# Sheet1_GMAX0505_MB.net
KiCad netlist of a schematic drawn in Altium Designer
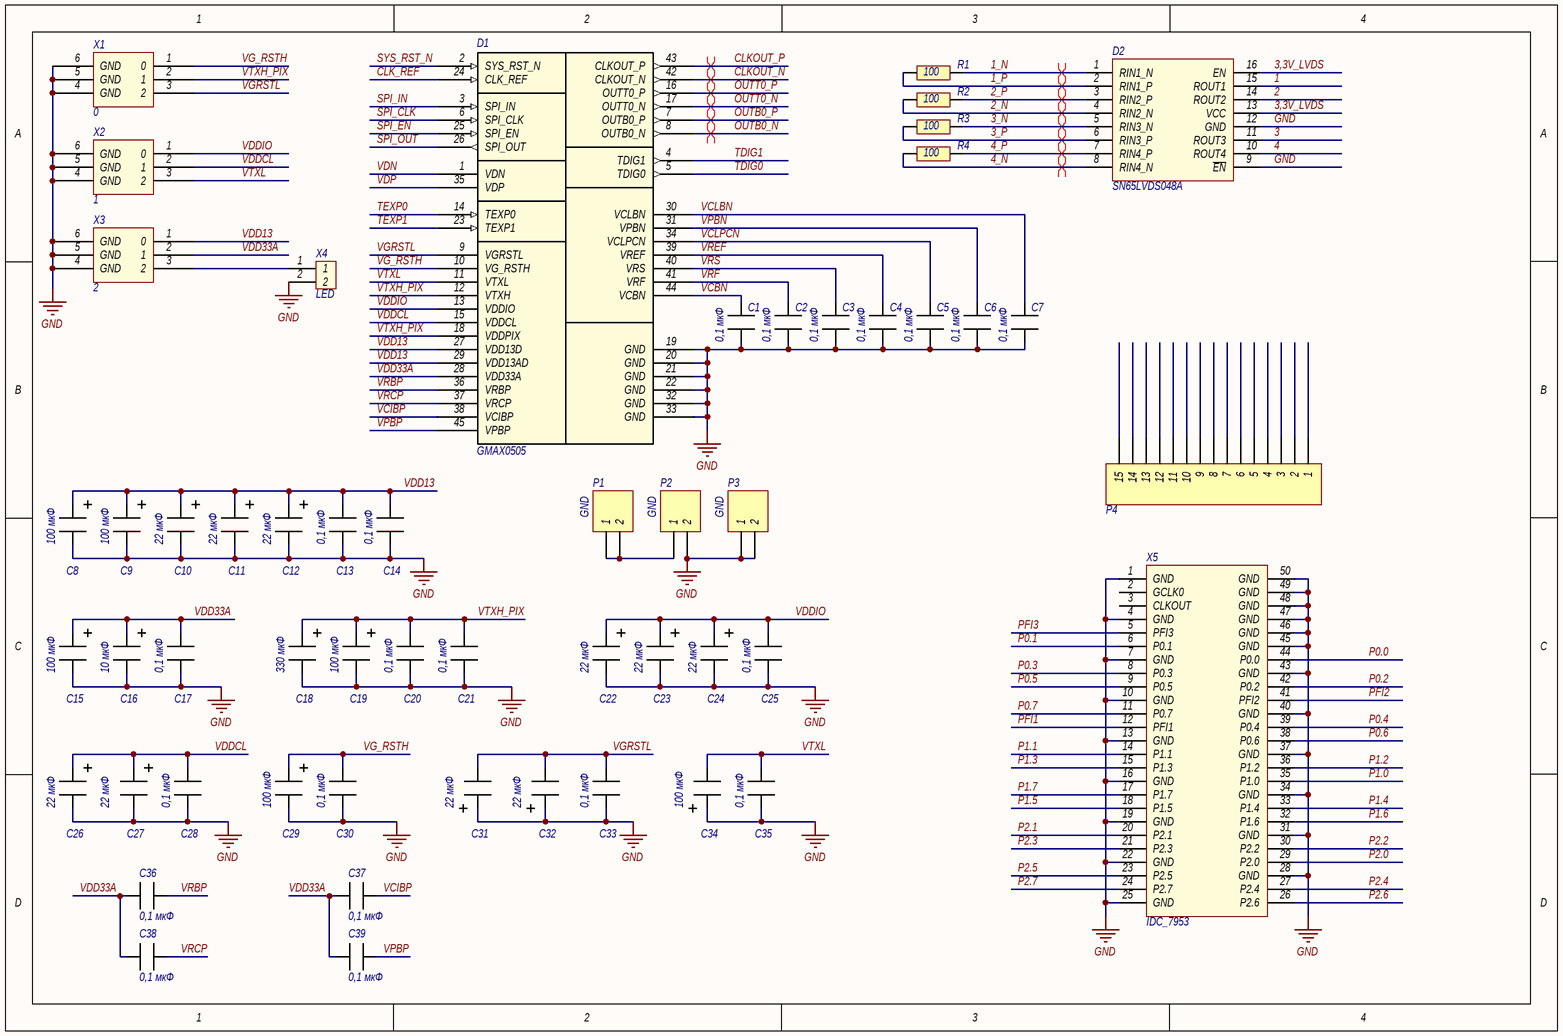
[diagram p0: Sheet1_GMAX0505_MB.SchDoc]

(export (version "E")
  (design (tool "Eeschema 10.0.6"))
  (components
    (comp (ref "C1") (value "0,1 мкФ") (footprint "CAP_SMALL") (libsource (lib "Schlib") (part "CAP_SMALL")))
    (comp (ref "C2") (value "0,1 мкФ") (footprint "CAP_SMALL") (libsource (lib "Schlib") (part "CAP_SMALL")))
    (comp (ref "C3") (value "0,1 мкФ") (footprint "CAP_SMALL") (libsource (lib "Schlib") (part "CAP_SMALL")))
    (comp (ref "C4") (value "0,1 мкФ") (footprint "CAP_SMALL") (libsource (lib "Schlib") (part "CAP_SMALL")))
    (comp (ref "C5") (value "0,1 мкФ") (footprint "CAP_SMALL") (libsource (lib "Schlib") (part "CAP_SMALL")))
    (comp (ref "C6") (value "0,1 мкФ") (footprint "CAP_SMALL") (libsource (lib "Schlib") (part "CAP_SMALL")))
    (comp (ref "C7") (value "0,1 мкФ") (footprint "CAP_SMALL") (libsource (lib "Schlib") (part "CAP_SMALL")))
    (comp (ref "C8")
      (value "100 мкФ")
      (footprint "Cap_0612_electrolitic")
      (libsource (lib "Schlib") (part "Cap_electrolotoc_0612"))
    )
    (comp (ref "C9")
      (value "100 мкФ")
      (footprint "Cap_0612_electrolitic")
      (libsource (lib "Schlib") (part "Cap_electrolotoc_0612"))
    )
    (comp (ref "C10")
      (value "22 мкФ")
      (footprint "Cap_0511_electrolitic")
      (libsource (lib "Schlib") (part "Cap_electrolotoc_0511"))
    )
    (comp (ref "C11")
      (value "22 мкФ")
      (footprint "Cap_0511_electrolitic")
      (libsource (lib "Schlib") (part "Cap_electrolotoc_0511"))
    )
    (comp (ref "C12")
      (value "22 мкФ")
      (footprint "Cap_0511_electrolitic")
      (libsource (lib "Schlib") (part "Cap_electrolotoc_0511"))
    )
    (comp (ref "C13") (value "0,1 мкФ") (footprint "CAP_SMALL") (libsource (lib "Schlib") (part "CAP_SMALL")))
    (comp (ref "C14") (value "0,1 мкФ") (footprint "CAP_SMALL") (libsource (lib "Schlib") (part "CAP_SMALL")))
    (comp (ref "C15")
      (value "100 мкФ")
      (footprint "Cap_0612_electrolitic")
      (libsource (lib "Schlib") (part "Cap_electrolotoc_0612"))
    )
    (comp (ref "C16")
      (value "10 мкФ")
      (footprint "Cap_0511_electrolitic")
      (libsource (lib "Schlib") (part "Cap_electrolotoc_0511"))
    )
    (comp (ref "C17") (value "0,1 мкФ") (footprint "CAP_SMALL") (libsource (lib "Schlib") (part "CAP_SMALL")))
    (comp (ref "C18")
      (value "330 мкФ")
      (footprint "Cap_1013_electrolitic")
      (libsource (lib "Schlib") (part "Cap_electrolotoc_1013"))
    )
    (comp (ref "C19")
      (value "100 мкФ")
      (footprint "Cap_0612_electrolitic")
      (libsource (lib "Schlib") (part "Cap_electrolotoc_0612"))
    )
    (comp (ref "C20") (value "0,1 мкФ") (footprint "CAP_SMALL") (libsource (lib "Schlib") (part "CAP_SMALL")))
    (comp (ref "C21") (value "0,1 мкФ") (footprint "CAP_SMALL") (libsource (lib "Schlib") (part "CAP_SMALL")))
    (comp (ref "C22")
      (value "22 мкФ")
      (footprint "Cap_0511_electrolitic")
      (libsource (lib "Schlib") (part "Cap_electrolotoc_0511"))
    )
    (comp (ref "C23")
      (value "22 мкФ")
      (footprint "Cap_0511_electrolitic")
      (libsource (lib "Schlib") (part "Cap_electrolotoc_0511"))
    )
    (comp (ref "C24")
      (value "22 мкФ")
      (footprint "Cap_0511_electrolitic")
      (libsource (lib "Schlib") (part "Cap_electrolotoc_0511"))
    )
    (comp (ref "C25") (value "0,1 мкФ") (footprint "CAP_SMALL") (libsource (lib "Schlib") (part "CAP_SMALL")))
    (comp (ref "C26")
      (value "22 мкФ")
      (footprint "Cap_0511_electrolitic")
      (libsource (lib "Schlib") (part "Cap_electrolotoc_0511"))
    )
    (comp (ref "C27")
      (value "22 мкФ")
      (footprint "Cap_0511_electrolitic")
      (libsource (lib "Schlib") (part "Cap_electrolotoc_0511"))
    )
    (comp (ref "C28") (value "0,1 мкФ") (footprint "CAP_SMALL") (libsource (lib "Schlib") (part "CAP_SMALL")))
    (comp (ref "C29")
      (value "100 мкФ")
      (footprint "Cap_0612_electrolitic")
      (libsource (lib "Schlib") (part "Cap_electrolotoc_0612"))
    )
    (comp (ref "C30") (value "0,1 мкФ") (footprint "CAP_SMALL") (libsource (lib "Schlib") (part "CAP_SMALL")))
    (comp (ref "C31")
      (value "22 мкФ")
      (footprint "Cap_0511_electrolitic")
      (libsource (lib "Schlib") (part "Cap_electrolotoc_0511"))
    )
    (comp (ref "C32")
      (value "22 мкФ")
      (footprint "Cap_0511_electrolitic")
      (libsource (lib "Schlib") (part "Cap_electrolotoc_0511"))
    )
    (comp (ref "C33") (value "0,1 мкФ") (footprint "CAP_SMALL") (libsource (lib "Schlib") (part "CAP_SMALL")))
    (comp (ref "C34")
      (value "100 мкФ")
      (footprint "Cap_0612_electrolitic")
      (libsource (lib "Schlib") (part "Cap_electrolotoc_0612"))
    )
    (comp (ref "C35") (value "0,1 мкФ") (footprint "CAP_SMALL") (libsource (lib "Schlib") (part "CAP_SMALL")))
    (comp (ref "C36") (value "0,1 мкФ") (footprint "CAP_SMALL") (libsource (lib "Schlib") (part "CAP_SMALL")))
    (comp (ref "C37") (value "0,1 мкФ") (footprint "CAP_SMALL") (libsource (lib "Schlib") (part "CAP_SMALL")))
    (comp (ref "C38") (value "0,1 мкФ") (footprint "CAP_SMALL") (libsource (lib "Schlib") (part "CAP_SMALL")))
    (comp (ref "C39") (value "0,1 мкФ") (footprint "CAP_SMALL") (libsource (lib "Schlib") (part "CAP_SMALL")))
    (comp (ref "D1")
      (value "GMAX0505")
      (footprint "GMAX0505_MEZ")
      (libsource (lib "Schlib") (part "GMAX0505_MEZ"))
    )
    (comp (ref "D2")
      (value "SN65LVDS048A")
      (footprint "SN65LVDS048A (4LVDS)")
      (libsource (lib "Schlib") (part "SN65LVDS048A (4LVDS)"))
    )
    (comp (ref "P1")
      (value "GND")
      (footprint "HDR1X2")
      (description "Header, 2-Pin")
      (fields (field (name "PUBLISHER") "Altium Limited"))
      (libsource (lib "Miscellaneous Connectors") (part "Header 2"))
    )
    (comp (ref "P2")
      (value "GND")
      (footprint "HDR1X2")
      (description "Header, 2-Pin")
      (fields (field (name "PUBLISHER") "Altium Limited"))
      (libsource (lib "Miscellaneous Connectors") (part "Header 2"))
    )
    (comp (ref "P3")
      (value "GND")
      (footprint "HDR1X2")
      (description "Header, 2-Pin")
      (fields (field (name "PUBLISHER") "Altium Limited"))
      (libsource (lib "Miscellaneous Connectors") (part "Header 2"))
    )
    (comp (ref "P4")
      (value "Header 15")
      (footprint "HDR1X15")
      (description "Header, 15-Pin")
      (fields (field (name "PUBLISHER") "Altium Limited"))
      (libsource (lib "Miscellaneous Connectors") (part "Header 15"))
    )
    (comp (ref "R1") (value "100") (footprint "RES") (libsource (lib "Schlib") (part "RES")))
    (comp (ref "R2") (value "100") (footprint "RES") (libsource (lib "Schlib") (part "RES")))
    (comp (ref "R3") (value "100") (footprint "RES") (libsource (lib "Schlib") (part "RES")))
    (comp (ref "R4") (value "100") (footprint "RES") (libsource (lib "Schlib") (part "RES")))
    (comp (ref "X1") (value "0") (footprint "POWER") (libsource (lib "Schlib") (part "POWER")))
    (comp (ref "X2") (value "1") (footprint "POWER") (libsource (lib "Schlib") (part "POWER")))
    (comp (ref "X3") (value "2") (footprint "POWER") (libsource (lib "Schlib") (part "POWER")))
    (comp (ref "X4") (value "LED") (footprint "KLEMMNIK_2") (libsource (lib "Schlib") (part "KLEMMNIK_2")))
    (comp (ref "X5") (value "IDC_7953") (footprint "IDC_7953") (libsource (lib "VPL") (part "IDC_7953")))
  )
  (nets
    (net (code "1") (name "/1") (class "Default")
      (node (ref "D2") (pin "15") (pinfunction "ROUT1_15") (pintype "passive"))
    )
    (net (code "2") (name "/1_N") (class "Default")
      (node (ref "D2") (pin "1") (pinfunction "RIN1_N_1") (pintype "passive"))
      (node (ref "R1") (pin "1") (pinfunction "1_1") (pintype "passive"))
    )
    (net (code "3") (name "/1_P") (class "Default")
      (node (ref "D2") (pin "2") (pinfunction "RIN1_P_2") (pintype "passive"))
      (node (ref "R1") (pin "2") (pinfunction "2_2") (pintype "passive"))
    )
    (net (code "4") (name "/2") (class "Default")
      (node (ref "D2") (pin "14") (pinfunction "ROUT2_14") (pintype "passive"))
    )
    (net (code "5") (name "/2_N") (class "Default")
      (node (ref "D2") (pin "4") (pinfunction "RIN2_N_4") (pintype "passive"))
      (node (ref "R2") (pin "2") (pinfunction "2_2") (pintype "passive"))
    )
    (net (code "6") (name "/2_P") (class "Default")
      (node (ref "D2") (pin "3") (pinfunction "RIN2_P_3") (pintype "passive"))
      (node (ref "R2") (pin "1") (pinfunction "1_1") (pintype "passive"))
    )
    (net (code "7") (name "/3") (class "Default")
      (node (ref "D2") (pin "11") (pinfunction "ROUT3_11") (pintype "passive"))
    )
    (net (code "8") (name "/3,3V_LVDS") (class "Default")
      (node (ref "D2") (pin "13") (pinfunction "VCC_13") (pintype "passive"))
      (node (ref "D2") (pin "16") (pinfunction "EN_16") (pintype "passive"))
    )
    (net (code "9") (name "/3_N") (class "Default")
      (node (ref "D2") (pin "5") (pinfunction "RIN3_N_5") (pintype "passive"))
      (node (ref "R3") (pin "1") (pinfunction "1_1") (pintype "passive"))
    )
    (net (code "10") (name "/3_P") (class "Default")
      (node (ref "D2") (pin "6") (pinfunction "RIN3_P_6") (pintype "passive"))
      (node (ref "R3") (pin "2") (pinfunction "2_2") (pintype "passive"))
    )
    (net (code "11") (name "/4") (class "Default")
      (node (ref "D2") (pin "10") (pinfunction "ROUT4_10") (pintype "passive"))
    )
    (net (code "12") (name "/4_N") (class "Default")
      (node (ref "D2") (pin "8") (pinfunction "RIN4_N_8") (pintype "passive"))
      (node (ref "R4") (pin "2") (pinfunction "2_2") (pintype "passive"))
    )
    (net (code "13") (name "/4_P") (class "Default")
      (node (ref "D2") (pin "7") (pinfunction "RIN4_P_7") (pintype "passive"))
      (node (ref "R4") (pin "1") (pinfunction "1_1") (pintype "passive"))
    )
    (net (code "14") (name "/CLKOUT_N") (class "Default")
      (node (ref "D1") (pin "42") (pinfunction "CLKOUT_N_42") (pintype "output"))
    )
    (net (code "15") (name "/CLKOUT_P") (class "Default")
      (node (ref "D1") (pin "43") (pinfunction "CLKOUT_P_43") (pintype "output"))
    )
    (net (code "16") (name "/CLK_REF") (class "Default")
      (node (ref "D1") (pin "24") (pinfunction "CLK_REF_24") (pintype "input"))
    )
    (net (code "17") (name "/OUTB0_N") (class "Default")
      (node (ref "D1") (pin "8") (pinfunction "OUTB0_N_8") (pintype "output"))
    )
    (net (code "18") (name "/OUTB0_P") (class "Default")
      (node (ref "D1") (pin "7") (pinfunction "OUTB0_P_7") (pintype "output"))
    )
    (net (code "19") (name "/OUTT0_N") (class "Default")
      (node (ref "D1") (pin "17") (pinfunction "OUTT0_N_17") (pintype "output"))
    )
    (net (code "20") (name "/OUTT0_P") (class "Default")
      (node (ref "D1") (pin "16") (pinfunction "OUTT0_P_16") (pintype "output"))
    )
    (net (code "21") (name "/P0.0") (class "Default")
      (node (ref "X5") (pin "44") (pinfunction "P0.0_44") (pintype "passive"))
    )
    (net (code "22") (name "/P0.1") (class "Default")
      (node (ref "X5") (pin "6") (pinfunction "P0.1_6") (pintype "passive"))
    )
    (net (code "23") (name "/P0.2") (class "Default")
      (node (ref "X5") (pin "42") (pinfunction "P0.2_42") (pintype "passive"))
    )
    (net (code "24") (name "/P0.3") (class "Default")
      (node (ref "X5") (pin "8") (pinfunction "P0.3_8") (pintype "passive"))
    )
    (net (code "25") (name "/P0.4") (class "Default")
      (node (ref "X5") (pin "39") (pinfunction "P0.4_39") (pintype "passive"))
    )
    (net (code "26") (name "/P0.5") (class "Default")
      (node (ref "X5") (pin "9") (pinfunction "P0.5_9") (pintype "passive"))
    )
    (net (code "27") (name "/P0.6") (class "Default")
      (node (ref "X5") (pin "38") (pinfunction "P0.6_38") (pintype "passive"))
    )
    (net (code "28") (name "/P0.7") (class "Default")
      (node (ref "X5") (pin "11") (pinfunction "P0.7_11") (pintype "passive"))
    )
    (net (code "29") (name "/P1.0") (class "Default")
      (node (ref "X5") (pin "35") (pinfunction "P1.0_35") (pintype "passive"))
    )
    (net (code "30") (name "/P1.1") (class "Default")
      (node (ref "X5") (pin "14") (pinfunction "P1.1_14") (pintype "passive"))
    )
    (net (code "31") (name "/P1.2") (class "Default")
      (node (ref "X5") (pin "36") (pinfunction "P1.2_36") (pintype "passive"))
    )
    (net (code "32") (name "/P1.3") (class "Default")
      (node (ref "X5") (pin "15") (pinfunction "P1.3_15") (pintype "passive"))
    )
    (net (code "33") (name "/P1.4") (class "Default")
      (node (ref "X5") (pin "33") (pinfunction "P1.4_33") (pintype "passive"))
    )
    (net (code "34") (name "/P1.5") (class "Default")
      (node (ref "X5") (pin "18") (pinfunction "P1.5_18") (pintype "passive"))
    )
    (net (code "35") (name "/P1.6") (class "Default")
      (node (ref "X5") (pin "32") (pinfunction "P1.6_32") (pintype "passive"))
    )
    (net (code "36") (name "/P1.7") (class "Default")
      (node (ref "X5") (pin "17") (pinfunction "P1.7_17") (pintype "passive"))
    )
    (net (code "37") (name "/P2.0") (class "Default")
      (node (ref "X5") (pin "29") (pinfunction "P2.0_29") (pintype "passive"))
    )
    (net (code "38") (name "/P2.1") (class "Default")
      (node (ref "X5") (pin "20") (pinfunction "P2.1_20") (pintype "passive"))
    )
    (net (code "39") (name "/P2.2") (class "Default")
      (node (ref "X5") (pin "30") (pinfunction "P2.2_30") (pintype "passive"))
    )
    (net (code "40") (name "/P2.3") (class "Default")
      (node (ref "X5") (pin "21") (pinfunction "P2.3_21") (pintype "passive"))
    )
    (net (code "41") (name "/P2.4") (class "Default")
      (node (ref "X5") (pin "27") (pinfunction "P2.4_27") (pintype "passive"))
    )
    (net (code "42") (name "/P2.5") (class "Default")
      (node (ref "X5") (pin "23") (pinfunction "P2.5_23") (pintype "passive"))
    )
    (net (code "43") (name "/P2.6") (class "Default")
      (node (ref "X5") (pin "26") (pinfunction "P2.6_26") (pintype "passive"))
    )
    (net (code "44") (name "/P2.7") (class "Default")
      (node (ref "X5") (pin "24") (pinfunction "P2.7_24") (pintype "passive"))
    )
    (net (code "45") (name "/PFI1") (class "Default")
      (node (ref "X5") (pin "12") (pinfunction "PFI1_12") (pintype "passive"))
    )
    (net (code "46") (name "/PFI2") (class "Default")
      (node (ref "X5") (pin "41") (pinfunction "PFI2_41") (pintype "passive"))
    )
    (net (code "47") (name "/PFI3") (class "Default")
      (node (ref "X5") (pin "5") (pinfunction "PFI3_5") (pintype "passive"))
    )
    (net (code "48") (name "/SPI_CLK") (class "Default")
      (node (ref "D1") (pin "6") (pinfunction "SPI_CLK_6") (pintype "input"))
    )
    (net (code "49") (name "/SPI_EN") (class "Default")
      (node (ref "D1") (pin "25") (pinfunction "SPI_EN_25") (pintype "input"))
    )
    (net (code "50") (name "/SPI_IN") (class "Default")
      (node (ref "D1") (pin "3") (pinfunction "SPI_IN_3") (pintype "input"))
    )
    (net (code "51") (name "/SPI_OUT") (class "Default")
      (node (ref "D1") (pin "26") (pinfunction "SPI_OUT_26") (pintype "output"))
    )
    (net (code "52") (name "/SYS_RST_N") (class "Default")
      (node (ref "D1") (pin "2") (pinfunction "SYS_RST_N_2") (pintype "input"))
    )
    (net (code "53") (name "/TDIG0") (class "Default")
      (node (ref "D1") (pin "5") (pinfunction "TDIG0_5") (pintype "output"))
    )
    (net (code "54") (name "/TDIG1") (class "Default")
      (node (ref "D1") (pin "4") (pinfunction "TDIG1_4") (pintype "output"))
    )
    (net (code "55") (name "/TEXP0") (class "Default")
      (node (ref "D1") (pin "14") (pinfunction "TEXP0_14") (pintype "input"))
    )
    (net (code "56") (name "/TEXP1") (class "Default")
      (node (ref "D1") (pin "23") (pinfunction "TEXP1_23") (pintype "input"))
    )
    (net (code "57") (name "/VCBN") (class "Default")
      (node (ref "C1") (pin "1") (pinfunction "1_1") (pintype "passive"))
      (node (ref "D1") (pin "44") (pinfunction "VCBN_44") (pintype "passive"))
    )
    (net (code "58") (name "/VCIBP") (class "Default")
      (node (ref "C37") (pin "1") (pinfunction "1_1") (pintype "passive"))
      (node (ref "D1") (pin "38") (pinfunction "VCIBP_38") (pintype "passive"))
    )
    (net (code "59") (name "/VCLBN") (class "Default")
      (node (ref "C7") (pin "1") (pinfunction "1_1") (pintype "passive"))
      (node (ref "D1") (pin "30") (pinfunction "VCLBN_30") (pintype "passive"))
    )
    (net (code "60") (name "/VCLPCN") (class "Default")
      (node (ref "C5") (pin "1") (pinfunction "1_1") (pintype "passive"))
      (node (ref "D1") (pin "34") (pinfunction "VCLPCN_34") (pintype "passive"))
    )
    (net (code "61") (name "/VDD13") (class "Default")
      (node (ref "C10") (pin "1") (pinfunction "1_1") (pintype "passive"))
      (node (ref "C11") (pin "1") (pinfunction "1_1") (pintype "passive"))
      (node (ref "C12") (pin "1") (pinfunction "1_1") (pintype "passive"))
      (node (ref "C13") (pin "1") (pinfunction "1_1") (pintype "passive"))
      (node (ref "C14") (pin "1") (pinfunction "1_1") (pintype "passive"))
      (node (ref "C8") (pin "1") (pinfunction "1_1") (pintype "passive"))
      (node (ref "C9") (pin "1") (pinfunction "1_1") (pintype "passive"))
      (node (ref "D1") (pin "27") (pinfunction "VDD13D_27") (pintype "passive"))
      (node (ref "D1") (pin "29") (pinfunction "VDD13AD_29") (pintype "passive"))
      (node (ref "X3") (pin "1") (pinfunction "0_1") (pintype "passive"))
    )
    (net (code "62") (name "/VDD33A") (class "Default")
      (node (ref "C15") (pin "1") (pinfunction "1_1") (pintype "passive"))
      (node (ref "C16") (pin "1") (pinfunction "1_1") (pintype "passive"))
      (node (ref "C17") (pin "1") (pinfunction "1_1") (pintype "passive"))
      (node (ref "C36") (pin "2") (pinfunction "2_2") (pintype "passive"))
      (node (ref "C37") (pin "2") (pinfunction "2_2") (pintype "passive"))
      (node (ref "C38") (pin "2") (pinfunction "2_2") (pintype "passive"))
      (node (ref "C39") (pin "2") (pinfunction "2_2") (pintype "passive"))
      (node (ref "D1") (pin "28") (pinfunction "VDD33A_28") (pintype "passive"))
      (node (ref "X3") (pin "2") (pinfunction "1_2") (pintype "passive"))
    )
    (net (code "63") (name "/VDDCL") (class "Default")
      (node (ref "C26") (pin "1") (pinfunction "1_1") (pintype "passive"))
      (node (ref "C27") (pin "1") (pinfunction "1_1") (pintype "passive"))
      (node (ref "C28") (pin "2") (pinfunction "2_2") (pintype "passive"))
      (node (ref "D1") (pin "15") (pinfunction "VDDCL_15") (pintype "passive"))
      (node (ref "X2") (pin "2") (pinfunction "1_2") (pintype "passive"))
    )
    (net (code "64") (name "/VDDIO") (class "Default")
      (node (ref "C22") (pin "1") (pinfunction "1_1") (pintype "passive"))
      (node (ref "C23") (pin "1") (pinfunction "1_1") (pintype "passive"))
      (node (ref "C24") (pin "1") (pinfunction "1_1") (pintype "passive"))
      (node (ref "C25") (pin "1") (pinfunction "1_1") (pintype "passive"))
      (node (ref "D1") (pin "13") (pinfunction "VDDIO_13") (pintype "passive"))
      (node (ref "X2") (pin "1") (pinfunction "0_1") (pintype "passive"))
    )
    (net (code "65") (name "/VDN") (class "Default")
      (node (ref "D1") (pin "1") (pinfunction "VDN_1") (pintype "passive"))
    )
    (net (code "66") (name "/VDP") (class "Default")
      (node (ref "D1") (pin "35") (pinfunction "VDP_35") (pintype "passive"))
    )
    (net (code "67") (name "/VGRSTL") (class "Default")
      (node (ref "C31") (pin "2") (pinfunction "2_2") (pintype "passive"))
      (node (ref "C32") (pin "2") (pinfunction "2_2") (pintype "passive"))
      (node (ref "C33") (pin "2") (pinfunction "2_2") (pintype "passive"))
      (node (ref "D1") (pin "9") (pinfunction "VGRSTL_9") (pintype "passive"))
      (node (ref "X1") (pin "3") (pinfunction "2_3") (pintype "passive"))
    )
    (net (code "68") (name "/VG_RSTH") (class "Default")
      (node (ref "C29") (pin "1") (pinfunction "1_1") (pintype "passive"))
      (node (ref "C30") (pin "1") (pinfunction "1_1") (pintype "passive"))
      (node (ref "D1") (pin "10") (pinfunction "VG_RSTH_10") (pintype "passive"))
      (node (ref "X1") (pin "1") (pinfunction "0_1") (pintype "passive"))
    )
    (net (code "69") (name "/VPBN") (class "Default")
      (node (ref "C6") (pin "1") (pinfunction "1_1") (pintype "passive"))
      (node (ref "D1") (pin "31") (pinfunction "VPBN_31") (pintype "passive"))
    )
    (net (code "70") (name "/VPBP") (class "Default")
      (node (ref "C39") (pin "1") (pinfunction "1_1") (pintype "passive"))
      (node (ref "D1") (pin "45") (pinfunction "VPBP_45") (pintype "passive"))
    )
    (net (code "71") (name "/VRBP") (class "Default")
      (node (ref "C36") (pin "1") (pinfunction "1_1") (pintype "passive"))
      (node (ref "D1") (pin "36") (pinfunction "VRBP_36") (pintype "passive"))
    )
    (net (code "72") (name "/VRCP") (class "Default")
      (node (ref "C38") (pin "1") (pinfunction "1_1") (pintype "passive"))
      (node (ref "D1") (pin "37") (pinfunction "VRCP_37") (pintype "passive"))
    )
    (net (code "73") (name "/VREF") (class "Default")
      (node (ref "C4") (pin "1") (pinfunction "1_1") (pintype "passive"))
      (node (ref "D1") (pin "39") (pinfunction "VREF_39") (pintype "passive"))
    )
    (net (code "74") (name "/VRF") (class "Default")
      (node (ref "C2") (pin "1") (pinfunction "1_1") (pintype "passive"))
      (node (ref "D1") (pin "41") (pinfunction "VRF_41") (pintype "passive"))
    )
    (net (code "75") (name "/VRS") (class "Default")
      (node (ref "C3") (pin "1") (pinfunction "1_1") (pintype "passive"))
      (node (ref "D1") (pin "40") (pinfunction "VRS_40") (pintype "passive"))
    )
    (net (code "76") (name "/VTXH_PIX") (class "Default")
      (node (ref "C18") (pin "1") (pinfunction "1_1") (pintype "passive"))
      (node (ref "C19") (pin "1") (pinfunction "1_1") (pintype "passive"))
      (node (ref "C20") (pin "1") (pinfunction "1_1") (pintype "passive"))
      (node (ref "C21") (pin "1") (pinfunction "1_1") (pintype "passive"))
      (node (ref "D1") (pin "12") (pinfunction "VTXH_12") (pintype "passive"))
      (node (ref "D1") (pin "18") (pinfunction "VDDPIX_18") (pintype "passive"))
      (node (ref "X1") (pin "2") (pinfunction "1_2") (pintype "passive"))
    )
    (net (code "77") (name "/VTXL") (class "Default")
      (node (ref "C34") (pin "2") (pinfunction "2_2") (pintype "passive"))
      (node (ref "C35") (pin "1") (pinfunction "1_1") (pintype "passive"))
      (node (ref "D1") (pin "11") (pinfunction "VTXL_11") (pintype "passive"))
      (node (ref "X2") (pin "3") (pinfunction "2_3") (pintype "passive"))
    )
    (net (code "78") (name "GND") (class "Default")
      (node (ref "C1") (pin "2") (pinfunction "2_2") (pintype "passive"))
      (node (ref "C10") (pin "2") (pinfunction "2_2") (pintype "passive"))
      (node (ref "C11") (pin "2") (pinfunction "2_2") (pintype "passive"))
      (node (ref "C12") (pin "2") (pinfunction "2_2") (pintype "passive"))
      (node (ref "C13") (pin "2") (pinfunction "2_2") (pintype "passive"))
      (node (ref "C14") (pin "2") (pinfunction "2_2") (pintype "passive"))
      (node (ref "C15") (pin "2") (pinfunction "2_2") (pintype "passive"))
      (node (ref "C16") (pin "2") (pinfunction "2_2") (pintype "passive"))
      (node (ref "C17") (pin "2") (pinfunction "2_2") (pintype "passive"))
      (node (ref "C18") (pin "2") (pinfunction "2_2") (pintype "passive"))
      (node (ref "C19") (pin "2") (pinfunction "2_2") (pintype "passive"))
      (node (ref "C2") (pin "2") (pinfunction "2_2") (pintype "passive"))
      (node (ref "C20") (pin "2") (pinfunction "2_2") (pintype "passive"))
      (node (ref "C21") (pin "2") (pinfunction "2_2") (pintype "passive"))
      (node (ref "C22") (pin "2") (pinfunction "2_2") (pintype "passive"))
      (node (ref "C23") (pin "2") (pinfunction "2_2") (pintype "passive"))
      (node (ref "C24") (pin "2") (pinfunction "2_2") (pintype "passive"))
      (node (ref "C25") (pin "2") (pinfunction "2_2") (pintype "passive"))
      (node (ref "C26") (pin "2") (pinfunction "2_2") (pintype "passive"))
      (node (ref "C27") (pin "2") (pinfunction "2_2") (pintype "passive"))
      (node (ref "C28") (pin "1") (pinfunction "1_1") (pintype "passive"))
      (node (ref "C29") (pin "2") (pinfunction "2_2") (pintype "passive"))
      (node (ref "C3") (pin "2") (pinfunction "2_2") (pintype "passive"))
      (node (ref "C30") (pin "2") (pinfunction "2_2") (pintype "passive"))
      (node (ref "C31") (pin "1") (pinfunction "1_1") (pintype "passive"))
      (node (ref "C32") (pin "1") (pinfunction "1_1") (pintype "passive"))
      (node (ref "C33") (pin "1") (pinfunction "1_1") (pintype "passive"))
      (node (ref "C34") (pin "1") (pinfunction "1_1") (pintype "passive"))
      (node (ref "C35") (pin "2") (pinfunction "2_2") (pintype "passive"))
      (node (ref "C4") (pin "2") (pinfunction "2_2") (pintype "passive"))
      (node (ref "C5") (pin "2") (pinfunction "2_2") (pintype "passive"))
      (node (ref "C6") (pin "2") (pinfunction "2_2") (pintype "passive"))
      (node (ref "C7") (pin "2") (pinfunction "2_2") (pintype "passive"))
      (node (ref "C8") (pin "2") (pinfunction "2_2") (pintype "passive"))
      (node (ref "C9") (pin "2") (pinfunction "2_2") (pintype "passive"))
      (node (ref "D1") (pin "19") (pinfunction "GND_19") (pintype "passive"))
      (node (ref "D1") (pin "20") (pinfunction "GND_20") (pintype "passive"))
      (node (ref "D1") (pin "21") (pinfunction "GND_21") (pintype "passive"))
      (node (ref "D1") (pin "22") (pinfunction "GND_22") (pintype "passive"))
      (node (ref "D1") (pin "32") (pinfunction "GND_32") (pintype "passive"))
      (node (ref "D1") (pin "33") (pinfunction "GND_33") (pintype "passive"))
      (node (ref "D2") (pin "12") (pinfunction "GND_12") (pintype "passive"))
      (node (ref "D2") (pin "9") (pinfunction "~{EN}_9") (pintype "passive"))
      (node (ref "P2") (pin "2") (pinfunction "2_2") (pintype "passive"))
      (node (ref "P3") (pin "1") (pinfunction "1_1") (pintype "passive"))
      (node (ref "P3") (pin "2") (pinfunction "2_2") (pintype "passive"))
      (node (ref "X1") (pin "4") (pinfunction "GND_4") (pintype "passive"))
      (node (ref "X1") (pin "5") (pinfunction "GND_5") (pintype "passive"))
      (node (ref "X1") (pin "6") (pinfunction "GND_6") (pintype "passive"))
      (node (ref "X2") (pin "4") (pinfunction "GND_4") (pintype "passive"))
      (node (ref "X2") (pin "5") (pinfunction "GND_5") (pintype "passive"))
      (node (ref "X2") (pin "6") (pinfunction "GND_6") (pintype "passive"))
      (node (ref "X3") (pin "4") (pinfunction "GND_4") (pintype "passive"))
      (node (ref "X3") (pin "5") (pinfunction "GND_5") (pintype "passive"))
      (node (ref "X3") (pin "6") (pinfunction "GND_6") (pintype "passive"))
      (node (ref "X4") (pin "2") (pinfunction "2_2") (pintype "passive"))
      (node (ref "X5") (pin "1") (pinfunction "GND_1") (pintype "passive"))
      (node (ref "X5") (pin "10") (pinfunction "GND_10") (pintype "passive"))
      (node (ref "X5") (pin "13") (pinfunction "GND_13") (pintype "passive"))
      (node (ref "X5") (pin "16") (pinfunction "GND_16") (pintype "passive"))
      (node (ref "X5") (pin "19") (pinfunction "GND_19") (pintype "passive"))
      (node (ref "X5") (pin "22") (pinfunction "GND_22") (pintype "passive"))
      (node (ref "X5") (pin "25") (pinfunction "GND_25") (pintype "passive"))
      (node (ref "X5") (pin "28") (pinfunction "GND_28") (pintype "passive"))
      (node (ref "X5") (pin "31") (pinfunction "GND_31") (pintype "passive"))
      (node (ref "X5") (pin "34") (pinfunction "GND_34") (pintype "passive"))
      (node (ref "X5") (pin "37") (pinfunction "GND_37") (pintype "passive"))
      (node (ref "X5") (pin "4") (pinfunction "GND_4") (pintype "passive"))
      (node (ref "X5") (pin "40") (pinfunction "GND_40") (pintype "passive"))
      (node (ref "X5") (pin "43") (pinfunction "GND_43") (pintype "passive"))
      (node (ref "X5") (pin "45") (pinfunction "GND_45") (pintype "passive"))
      (node (ref "X5") (pin "46") (pinfunction "GND_46") (pintype "passive"))
      (node (ref "X5") (pin "47") (pinfunction "GND_47") (pintype "passive"))
      (node (ref "X5") (pin "48") (pinfunction "GND_48") (pintype "passive"))
      (node (ref "X5") (pin "49") (pinfunction "GND_49") (pintype "passive"))
      (node (ref "X5") (pin "50") (pinfunction "GND_50") (pintype "passive"))
      (node (ref "X5") (pin "7") (pinfunction "GND_7") (pintype "passive"))
    )
    (net (code "79") (name "Net-(P1-Pad1)") (class "Default")
      (node (ref "P1") (pin "1") (pinfunction "1_1") (pintype "passive"))
      (node (ref "P1") (pin "2") (pinfunction "2_2") (pintype "passive"))
      (node (ref "P2") (pin "1") (pinfunction "1_1") (pintype "passive"))
    )
    (net (code "80") (name "Net-(X3-2)") (class "Default")
      (node (ref "X3") (pin "3") (pinfunction "2_3") (pintype "passive"))
      (node (ref "X4") (pin "1") (pinfunction "1_1") (pintype "passive"))
    )
    (net (code "81") (name "unconnected-(P4-Pad1)") (class "Default")
      (node (ref "P4") (pin "1") (pinfunction "1_1") (pintype "passive"))
    )
    (net (code "82") (name "unconnected-(P4-Pad2)") (class "Default")
      (node (ref "P4") (pin "2") (pinfunction "2_2") (pintype "passive"))
    )
    (net (code "83") (name "unconnected-(P4-Pad3)") (class "Default")
      (node (ref "P4") (pin "3") (pinfunction "3_3") (pintype "passive"))
    )
    (net (code "84") (name "unconnected-(P4-Pad4)") (class "Default")
      (node (ref "P4") (pin "4") (pinfunction "4_4") (pintype "passive"))
    )
    (net (code "85") (name "unconnected-(P4-Pad5)") (class "Default")
      (node (ref "P4") (pin "5") (pinfunction "5_5") (pintype "passive"))
    )
    (net (code "86") (name "unconnected-(P4-Pad6)") (class "Default")
      (node (ref "P4") (pin "6") (pinfunction "6_6") (pintype "passive"))
    )
    (net (code "87") (name "unconnected-(P4-Pad7)") (class "Default")
      (node (ref "P4") (pin "7") (pinfunction "7_7") (pintype "passive"))
    )
    (net (code "88") (name "unconnected-(P4-Pad8)") (class "Default")
      (node (ref "P4") (pin "8") (pinfunction "8_8") (pintype "passive"))
    )
    (net (code "89") (name "unconnected-(P4-Pad9)") (class "Default")
      (node (ref "P4") (pin "9") (pinfunction "9_9") (pintype "passive"))
    )
    (net (code "90") (name "unconnected-(P4-Pad10)") (class "Default")
      (node (ref "P4") (pin "10") (pinfunction "10_10") (pintype "passive"))
    )
    (net (code "91") (name "unconnected-(P4-Pad11)") (class "Default")
      (node (ref "P4") (pin "11") (pinfunction "11_11") (pintype "passive"))
    )
    (net (code "92") (name "unconnected-(P4-Pad12)") (class "Default")
      (node (ref "P4") (pin "12") (pinfunction "12_12") (pintype "passive"))
    )
    (net (code "93") (name "unconnected-(P4-Pad13)") (class "Default")
      (node (ref "P4") (pin "13") (pinfunction "13_13") (pintype "passive"))
    )
    (net (code "94") (name "unconnected-(P4-Pad14)") (class "Default")
      (node (ref "P4") (pin "14") (pinfunction "14_14") (pintype "passive"))
    )
    (net (code "95") (name "unconnected-(P4-Pad15)") (class "Default")
      (node (ref "P4") (pin "15") (pinfunction "15_15") (pintype "passive"))
    )
    (net (code "96") (name "unconnected-(X5-CLKOUT-Pad3)") (class "Default")
      (node (ref "X5") (pin "3") (pinfunction "CLKOUT_3") (pintype "passive"))
    )
    (net (code "97") (name "unconnected-(X5-GCLK0-Pad2)") (class "Default")
      (node (ref "X5") (pin "2") (pinfunction "GCLK0_2") (pintype "passive"))
    )
  )
)
